# BW1097_uSD.net
KiCad netlist of a schematic drawn in Altium Designer
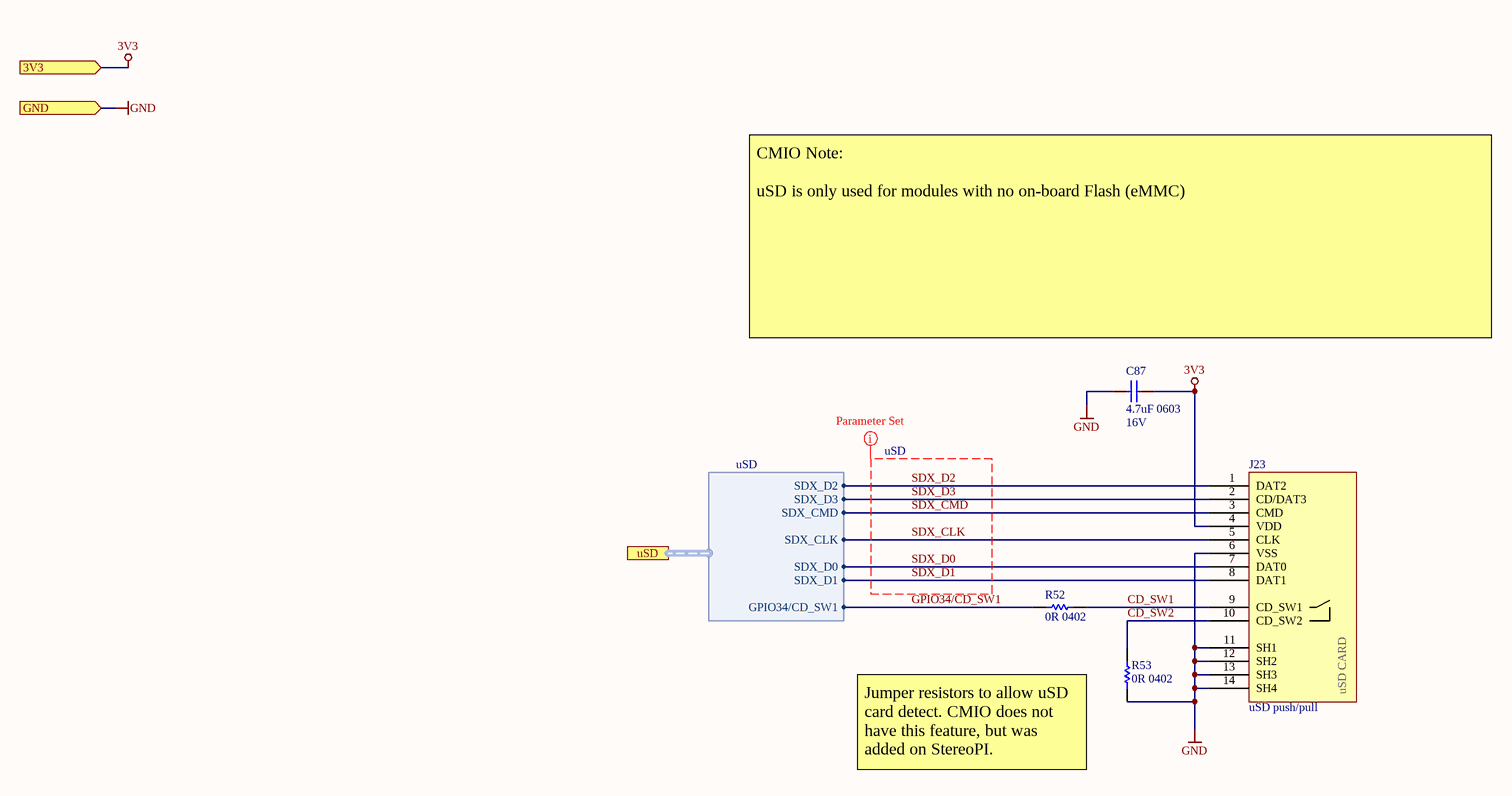
[diagram p0: BW1097_uSD.SchDoc]

(export (version "E")
  (design (tool "Eeschema 10.0.6"))
  (components
    (comp (ref "C87")
      (value "4.7uF 0603")
      (footprint "CAP_Altium_Vault_Generic:CAPC0603(1608)100_N")
      (description "CAP CER 4.7UF 16V X5R 0603 10%")
      (fields (field (name "TOLERANCE") "10%") (field (name "VOLTAGE RATING") "16V"))
      (libsource (lib "LuxonisMaster") (part "GRM188R61C475KAAJD"))
    )
    (comp (ref "J23")
      (value "uSD push/pull")
      (footprint "LuxonisMaster:104031-0811")
      (description "CONN MICRO SD CARD PUSH-PULL R/A")
      (libsource (lib "LuxonisMaster") (part "104031-0811"))
    )
    (comp (ref "R52")
      (value "0R 0402")
      (footprint "RES_Altium_Vault_Generic:RESC0402(1005)_N")
      (description "RES SMD 0 OHM JUMPER 1/16W 0402")
      (fields (field (name "TOLERANCE") "5%"))
      (libsource (lib "LuxonisMaster") (part "CRCW04020000Z0ED"))
    )
    (comp (ref "R53")
      (value "0R 0402")
      (footprint "RES_Altium_Vault_Generic:RESC0402(1005)_N")
      (description "RES SMD 0 OHM JUMPER 1/16W 0402")
      (fields (field (name "TOLERANCE") "5%"))
      (libsource (lib "LuxonisMaster") (part "CRCW04020000Z0ED"))
    )
  )
  (nets
    (net (code "2") (name "/CD_SW1") (class "Default")
      (node (ref "J23") (pin "9") (pinfunction "CD_SW1_9") (pintype "passive"))
      (node (ref "R52") (pin "1") (pinfunction "1_1") (pintype "passive"))
    )
    (net (code "3") (name "/CD_SW2") (class "Default")
      (node (ref "J23") (pin "10") (pinfunction "CD_SW2_10") (pintype "passive"))
      (node (ref "R53") (pin "2") (pinfunction "2_2") (pintype "passive"))
    )
    (net (code "4") (name "/GPIO34{slash}CD_SW1") (class "Default")
      (node (ref "R52") (pin "2") (pinfunction "2_2") (pintype "passive"))
    )
    (net (code "5") (name "/SDX_CLK") (class "Default")
      (node (ref "J23") (pin "5") (pinfunction "CLK_5") (pintype "passive"))
    )
    (net (code "6") (name "/SDX_CMD") (class "Default")
      (node (ref "J23") (pin "3") (pinfunction "CMD_3") (pintype "passive"))
    )
    (net (code "7") (name "/SDX_D0") (class "Default")
      (node (ref "J23") (pin "7") (pinfunction "DAT0_7") (pintype "passive"))
    )
    (net (code "8") (name "/SDX_D1") (class "Default")
      (node (ref "J23") (pin "8") (pinfunction "DAT1_8") (pintype "passive"))
    )
    (net (code "9") (name "/SDX_D2") (class "Default")
      (node (ref "J23") (pin "1") (pinfunction "DAT2_1") (pintype "passive"))
    )
    (net (code "10") (name "/SDX_D3") (class "Default")
      (node (ref "J23") (pin "2") (pinfunction "CD/DAT3_2") (pintype "passive"))
    )
    (net (code "12") (name "3V3") (class "Default")
      (node (ref "C87") (pin "2") (pinfunction "2_2") (pintype "passive"))
      (node (ref "J23") (pin "4") (pinfunction "VDD_4") (pintype "passive"))
    )
    (net (code "13") (name "GND") (class "Default")
      (node (ref "C87") (pin "1") (pinfunction "1_1") (pintype "passive"))
      (node (ref "J23") (pin "11") (pinfunction "SH1_11") (pintype "passive"))
      (node (ref "J23") (pin "12") (pinfunction "SH2_12") (pintype "passive"))
      (node (ref "J23") (pin "13") (pinfunction "SH3_13") (pintype "passive"))
      (node (ref "J23") (pin "14") (pinfunction "SH4_14") (pintype "passive"))
      (node (ref "J23") (pin "6") (pinfunction "VSS_6") (pintype "passive"))
      (node (ref "R53") (pin "1") (pinfunction "1_1") (pintype "passive"))
    )
  )
)
